# RCMx1_Rev_04.net
KiCad netlist of a schematic drawn in EAGLE
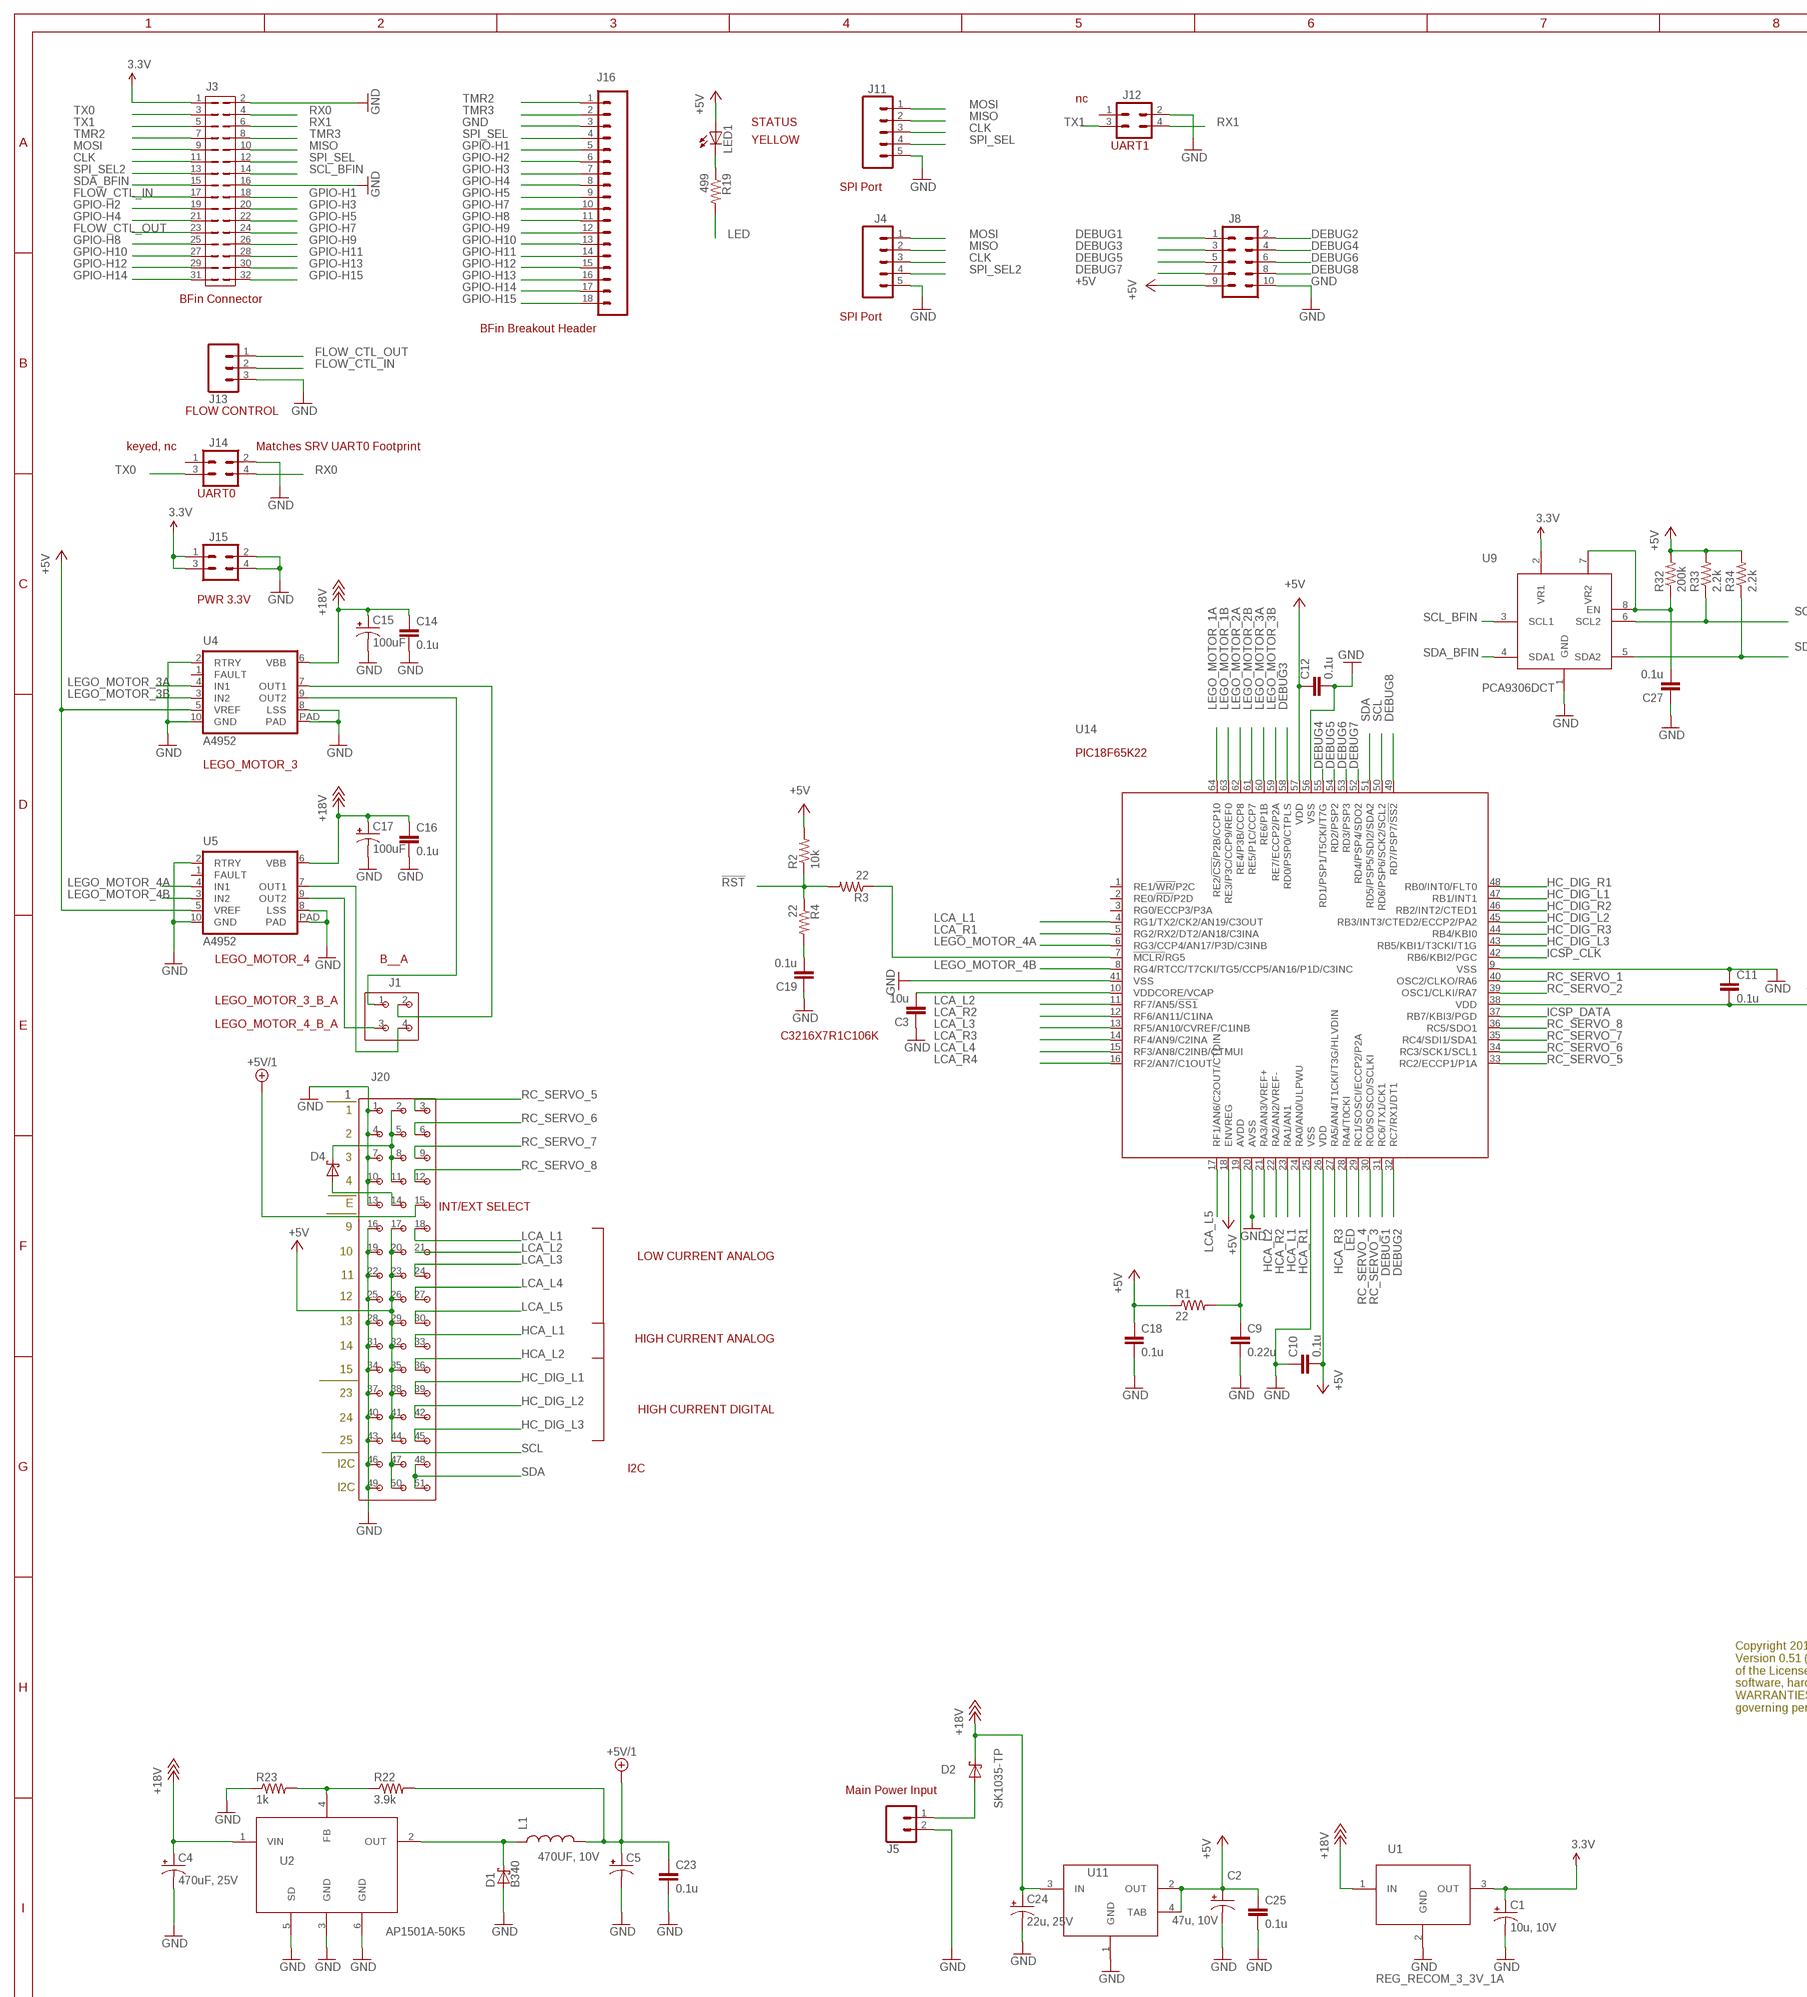
[diagram p0: schematic, sheet 1, part 1 of 2]
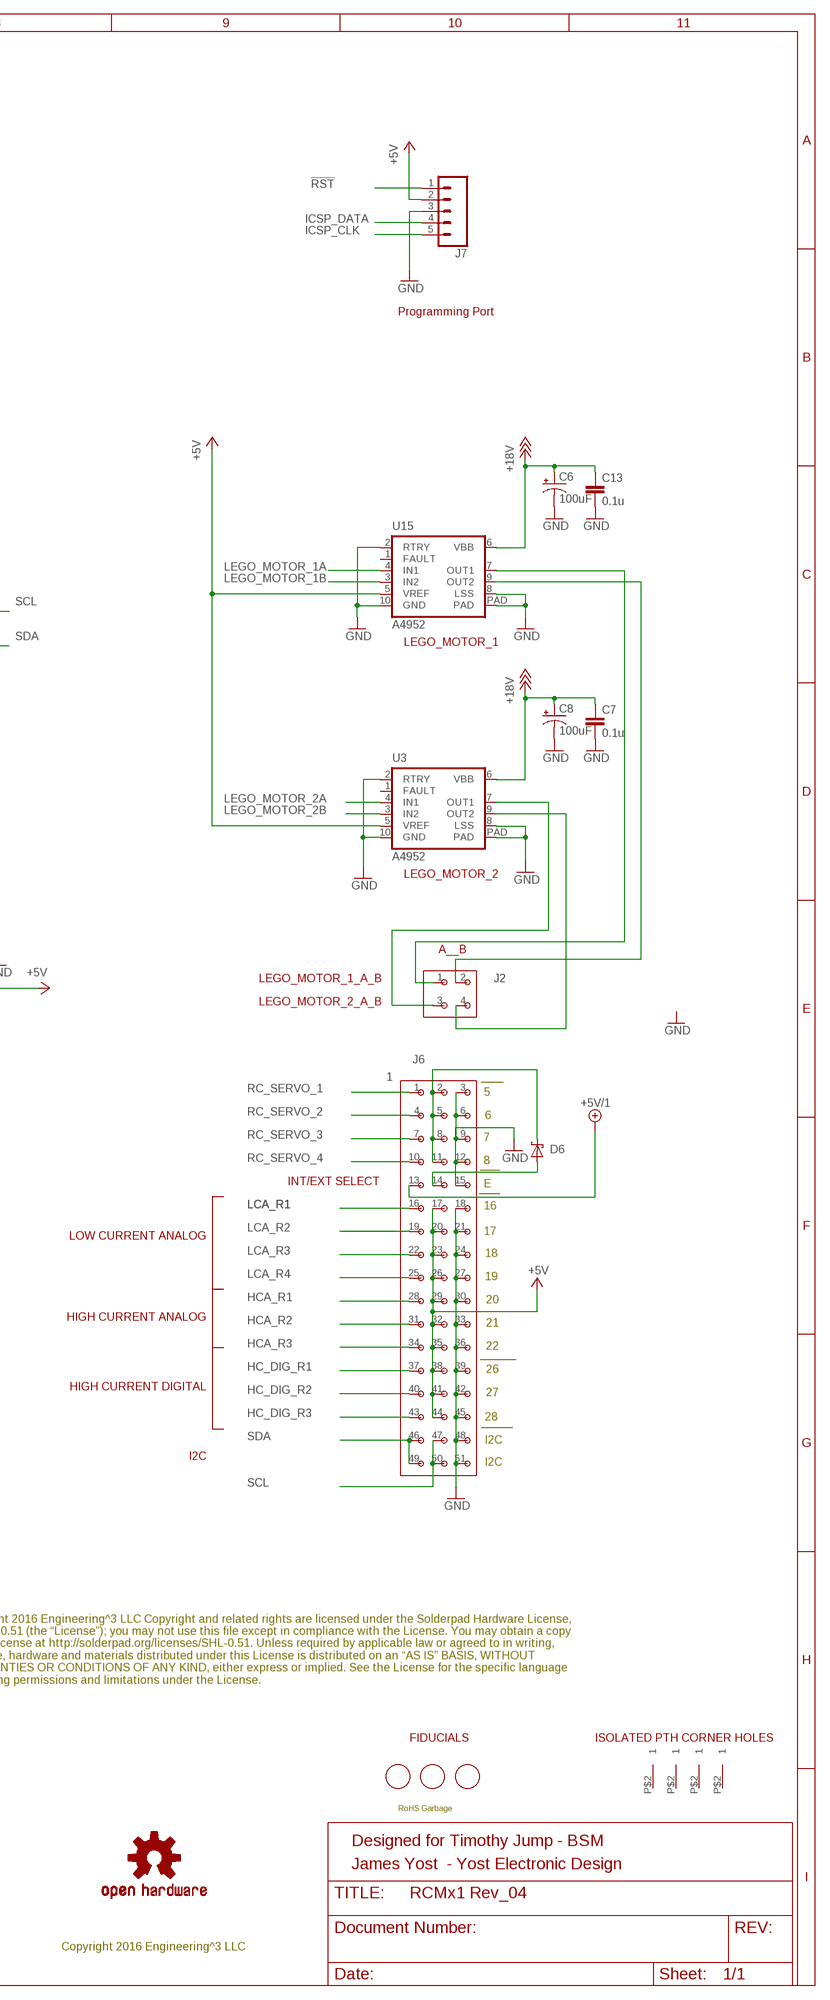
[diagram p1: schematic, sheet 1, part 2 of 2]

(export (version "E")
  (design (tool "Eeschema 10.0.6"))
  (components
    (comp (ref "C1")
      (value "10u, 10V")
      (footprint "eagle-import:EIA3216")
      (libsource (lib "eagle-import") (part "CAP_POL1206"))
    )
    (comp (ref "C2")
      (value "47u, 10V")
      (footprint "eagle-import:CAP1210_POL")
      (libsource (lib "eagle-import") (part "CAP_1210_POL"))
    )
    (comp (ref "C3")
      (value "10u")
      (footprint "eagle-import:1206")
      (libsource (lib "eagle-import") (part "CAP1206"))
    )
    (comp (ref "C4")
      (value "470uF, 25V")
      (footprint "eagle-import:PANASONIC_G")
      (libsource (lib "eagle-import") (part "CAP_POLG"))
    )
    (comp (ref "C5")
      (value "470UF, 10V")
      (footprint "eagle-import:PANASONIC_F")
      (libsource (lib "eagle-import") (part "CAP_ELT_PANASONIC_470UF"))
    )
    (comp (ref "C6")
      (value "100uF")
      (footprint "eagle-import:PANASONIC_D")
      (libsource (lib "eagle-import") (part "CAP_POLD"))
    )
    (comp (ref "C7")
      (value "0.1u")
      (footprint "eagle-import:0805")
      (libsource (lib "eagle-import") (part "CAP0805"))
    )
    (comp (ref "C8")
      (value "100uF")
      (footprint "eagle-import:PANASONIC_D")
      (libsource (lib "eagle-import") (part "CAP_POLD"))
    )
    (comp (ref "C9")
      (value "0.22u")
      (footprint "eagle-import:0805")
      (libsource (lib "eagle-import") (part "CAP0805"))
    )
    (comp (ref "C10")
      (value "0.1u")
      (footprint "eagle-import:0805")
      (libsource (lib "eagle-import") (part "CAP0805"))
    )
    (comp (ref "C11")
      (value "0.1u")
      (footprint "eagle-import:0805")
      (libsource (lib "eagle-import") (part "CAP0805"))
    )
    (comp (ref "C12")
      (value "0.1u")
      (footprint "eagle-import:0805")
      (libsource (lib "eagle-import") (part "CAP0805"))
    )
    (comp (ref "C13")
      (value "0.1u")
      (footprint "eagle-import:0805")
      (libsource (lib "eagle-import") (part "CAP0805"))
    )
    (comp (ref "C14")
      (value "0.1u")
      (footprint "eagle-import:0805")
      (libsource (lib "eagle-import") (part "CAP0805"))
    )
    (comp (ref "C15")
      (value "100uF")
      (footprint "eagle-import:PANASONIC_D")
      (libsource (lib "eagle-import") (part "CAP_POLD"))
    )
    (comp (ref "C16")
      (value "0.1u")
      (footprint "eagle-import:0805")
      (libsource (lib "eagle-import") (part "CAP0805"))
    )
    (comp (ref "C17")
      (value "100uF")
      (footprint "eagle-import:PANASONIC_D")
      (libsource (lib "eagle-import") (part "CAP_POLD"))
    )
    (comp (ref "C18")
      (value "0.1u")
      (footprint "eagle-import:0805")
      (libsource (lib "eagle-import") (part "CAP0805"))
    )
    (comp (ref "C19")
      (value "0.1u")
      (footprint "eagle-import:0805")
      (libsource (lib "eagle-import") (part "CAP0805"))
    )
    (comp (ref "C23")
      (value "0.1u")
      (footprint "eagle-import:0805")
      (libsource (lib "eagle-import") (part "CAP0805"))
    )
    (comp (ref "C24")
      (value "22u, 25V")
      (footprint "eagle-import:CAP1210_POL")
      (libsource (lib "eagle-import") (part "CAP_1210_POL"))
    )
    (comp (ref "C25")
      (value "0.1u")
      (footprint "eagle-import:0805")
      (libsource (lib "eagle-import") (part "CAP0805"))
    )
    (comp (ref "C27")
      (value "0.1u")
      (footprint "eagle-import:0805")
      (libsource (lib "eagle-import") (part "CAP0805"))
    )
    (comp (ref "D1")
      (value "B340")
      (footprint "eagle-import:SMA_DO214AC")
      (libsource (lib "eagle-import") (part "B340"))
    )
    (comp (ref "D2")
      (value "SK1035-TP")
      (footprint "eagle-import:DO214AB")
      (libsource (lib "eagle-import") (part "SK1035-TP"))
    )
    (comp (ref "D4")
      (value "SK1035-TP")
      (footprint "eagle-import:DO214AB")
      (libsource (lib "eagle-import") (part "SK1035-TP"))
    )
    (comp (ref "D6")
      (value "SK1035-TP")
      (footprint "eagle-import:DO214AB")
      (libsource (lib "eagle-import") (part "SK1035-TP"))
    )
    (comp (ref "FID1")
      (value "FIDUCIAL")
      (footprint "eagle-import:FIDUCIAL_1MM")
      (libsource (lib "eagle-import") (part "FIDUCIAL"))
    )
    (comp (ref "FID2")
      (value "FIDUCIAL")
      (footprint "eagle-import:FIDUCIAL_1MM")
      (libsource (lib "eagle-import") (part "FIDUCIAL"))
    )
    (comp (ref "FID3")
      (value "FIDUCIAL")
      (footprint "eagle-import:FIDUCIAL_1MM")
      (libsource (lib "eagle-import") (part "FIDUCIAL"))
    )
    (comp (ref "J1")
      (value "CON_2X2_0_100")
      (footprint "eagle-import:CON_2X2_0_100")
      (libsource (lib "eagle-import") (part "CON_2X2_0_100"))
    )
    (comp (ref "J2")
      (value "CON_2X2_0_100")
      (footprint "eagle-import:CON_2X2_0_100")
      (libsource (lib "eagle-import") (part "CON_2X2_0_100"))
    )
    (comp (ref "J3")
      (value "CON_2X16_0_100")
      (footprint "eagle-import:CON_2X16_0_100")
      (libsource (lib "eagle-import") (part "CON_2X16_0_100"))
    )
    (comp (ref "J4")
      (value "M05PTH")
      (footprint "eagle-import:1X05")
      (libsource (lib "eagle-import") (part "M05PTH"))
    )
    (comp (ref "J5")
      (value "M02NG")
      (footprint "eagle-import:1X02")
      (libsource (lib "eagle-import") (part "M02NG"))
    )
    (comp (ref "J6")
      (value "CON_3X17_0_100")
      (footprint "eagle-import:CON_3X17_0_100")
      (libsource (lib "eagle-import") (part "CON_3X17_0_100"))
    )
    (comp (ref "J7")
      (value "M05PTH")
      (footprint "eagle-import:1X05")
      (libsource (lib "eagle-import") (part "SparkFun-Connectors_M05PTH"))
    )
    (comp (ref "J8")
      (value "M05X2PTH")
      (footprint "eagle-import:AVR_ICSP")
      (libsource (lib "eagle-import") (part "M05X2PTH"))
    )
    (comp (ref "J11")
      (value "M05PTH")
      (footprint "eagle-import:1X05")
      (libsource (lib "eagle-import") (part "M05PTH"))
    )
    (comp (ref "J12")
      (value "CON2X2")
      (footprint "eagle-import:CON2X2")
      (libsource (lib "eagle-import") (part "CON2X2"))
    )
    (comp (ref "J13")
      (value "M03PTH")
      (footprint "eagle-import:1X03")
      (libsource (lib "eagle-import") (part "M03PTH"))
    )
    (comp (ref "J14")
      (value "CON2X2")
      (footprint "eagle-import:CON2X2")
      (libsource (lib "eagle-import") (part "CON2X2"))
    )
    (comp (ref "J15")
      (value "CON2X2")
      (footprint "eagle-import:CON2X2")
      (libsource (lib "eagle-import") (part "CON2X2"))
    )
    (comp (ref "J16")
      (value "CON1X18")
      (footprint "eagle-import:CON1X18")
      (libsource (lib "eagle-import") (part "CON1X18"))
    )
    (comp (ref "J20")
      (value "CON_3X17_0_100")
      (footprint "eagle-import:CON_3X17_0_100")
      (libsource (lib "eagle-import") (part "CON_3X17_0_100"))
    )
    (comp (ref "L1")
      (value "IND_47UH_COILTRONICS_2_95A")
      (footprint "eagle-import:IND_PADS_SMT")
      (libsource (lib "eagle-import") (part "IND_47UH_COILTRONICS_2_95A"))
    )
    (comp (ref "LED1")
      (value "LEDCHIP-LED0805")
      (footprint "eagle-import:CHIP-LED0805")
      (libsource (lib "eagle-import") (part "LEDCHIP-LED0805"))
    )
    (comp (ref "LOGO1")
      (value "OSHW-LOGOM")
      (footprint "eagle-import:OSHW-LOGO-M")
      (libsource (lib "eagle-import") (part "OSHW-LOGOM"))
    )
    (comp (ref "R1")
      (value "22")
      (footprint "eagle-import:0805")
      (libsource (lib "eagle-import") (part "RESISTOR"))
    )
    (comp (ref "R2")
      (value "10k")
      (footprint "eagle-import:0805")
      (libsource (lib "eagle-import") (part "RESISTOR"))
    )
    (comp (ref "R3")
      (value "22")
      (footprint "eagle-import:0805")
      (libsource (lib "eagle-import") (part "RESISTOR"))
    )
    (comp (ref "R4")
      (value "22")
      (footprint "eagle-import:0805")
      (libsource (lib "eagle-import") (part "RESISTOR"))
    )
    (comp (ref "R19")
      (value "499")
      (footprint "eagle-import:0805")
      (libsource (lib "eagle-import") (part "RESISTOR"))
    )
    (comp (ref "R22")
      (value "3.9k")
      (footprint "eagle-import:0805")
      (libsource (lib "eagle-import") (part "RESISTOR"))
    )
    (comp (ref "R23")
      (value "1k")
      (footprint "eagle-import:0805")
      (libsource (lib "eagle-import") (part "RESISTOR"))
    )
    (comp (ref "R32")
      (value "200k")
      (footprint "eagle-import:0805")
      (libsource (lib "eagle-import") (part "RESISTOR"))
    )
    (comp (ref "R33")
      (value "2.2k")
      (footprint "eagle-import:0805")
      (libsource (lib "eagle-import") (part "RESISTOR"))
    )
    (comp (ref "R34")
      (value "2.2k")
      (footprint "eagle-import:0805")
      (libsource (lib "eagle-import") (part "RESISTOR"))
    )
    (comp (ref "U$1")
      (value "GNDPAD")
      (footprint "eagle-import:GNDPAD")
      (libsource (lib "eagle-import") (part "GNDPAD"))
    )
    (comp (ref "U$2")
      (value "GNDPAD")
      (footprint "eagle-import:GNDPAD")
      (libsource (lib "eagle-import") (part "GNDPAD"))
    )
    (comp (ref "U$3")
      (value "ROHS_GARBAGE")
      (footprint "eagle-import:ROHS_GARBAGE_5MM")
      (libsource (lib "eagle-import") (part "ROHS_GARBAGE"))
    )
    (comp (ref "U$7")
      (value "GNDPAD")
      (footprint "eagle-import:GNDPAD")
      (libsource (lib "eagle-import") (part "GNDPAD"))
    )
    (comp (ref "U$8")
      (value "GNDPAD")
      (footprint "eagle-import:GNDPAD")
      (libsource (lib "eagle-import") (part "GNDPAD"))
    )
    (comp (ref "U1")
      (value "REG_RECOM_3_3V_1A")
      (footprint "eagle-import:REG_RECOM_3_3V_1A")
      (libsource (lib "eagle-import") (part "REG_RECOM_3_3V_1A"))
    )
    (comp (ref "U2")
      (value "AP1501A-50K5")
      (footprint "eagle-import:TO263-5")
      (libsource (lib "eagle-import") (part "AP1501A-50K5"))
    )
    (comp (ref "U3")
      (value "A4952")
      (footprint "eagle-import:MSOP10_W_THERMAL_PAD")
      (libsource (lib "eagle-import") (part "A4952"))
    )
    (comp (ref "U4")
      (value "A4952")
      (footprint "eagle-import:MSOP10_W_THERMAL_PAD")
      (libsource (lib "eagle-import") (part "A4952"))
    )
    (comp (ref "U5")
      (value "A4952")
      (footprint "eagle-import:MSOP10_W_THERMAL_PAD")
      (libsource (lib "eagle-import") (part "A4952"))
    )
    (comp (ref "U9")
      (value "PCA9306DCT")
      (footprint "eagle-import:TEST08")
      (libsource (lib "eagle-import") (part "PCA9306DCT"))
    )
    (comp (ref "U11")
      (value "TLV1117-5")
      (footprint "eagle-import:SOT223")
      (libsource (lib "eagle-import") (part "TLV1117-5"))
    )
    (comp (ref "U14")
      (value "MICRO_C_PIC18F65K22")
      (footprint "eagle-import:64PIN_TQFP_10X10X1MM")
      (libsource (lib "eagle-import") (part "MICRO_C_PIC18F65K22"))
    )
    (comp (ref "U15")
      (value "A4952")
      (footprint "eagle-import:MSOP10_W_THERMAL_PAD")
      (libsource (lib "eagle-import") (part "A4952"))
    )
  )
  (nets
    (net (code "1") (name "+5V") (class "Default")
      (node (ref "C10") (pin "2") (pinfunction "2_2") (pintype "passive"))
      (node (ref "C11") (pin "2") (pinfunction "2_2") (pintype "passive"))
      (node (ref "C12") (pin "1") (pinfunction "1_1") (pintype "passive"))
      (node (ref "C18") (pin "1") (pinfunction "1_1") (pintype "passive"))
      (node (ref "C2") (pin "1") (pinfunction "+_1") (pintype "passive"))
      (node (ref "C25") (pin "1") (pinfunction "1_1") (pintype "passive"))
      (node (ref "J20") (pin "17") (pinfunction "17_17") (pintype "passive"))
      (node (ref "J20") (pin "20") (pinfunction "20_20") (pintype "passive"))
      (node (ref "J20") (pin "23") (pinfunction "23_23") (pintype "passive"))
      (node (ref "J20") (pin "26") (pinfunction "26_26") (pintype "passive"))
      (node (ref "J20") (pin "29") (pinfunction "29_29") (pintype "passive"))
      (node (ref "J20") (pin "32") (pinfunction "32_32") (pintype "passive"))
      (node (ref "J20") (pin "35") (pinfunction "35_35") (pintype "passive"))
      (node (ref "J20") (pin "38") (pinfunction "38_38") (pintype "passive"))
      (node (ref "J20") (pin "41") (pinfunction "41_41") (pintype "passive"))
      (node (ref "J20") (pin "44") (pinfunction "44_44") (pintype "passive"))
      (node (ref "J6") (pin "17") (pinfunction "17_17") (pintype "passive"))
      (node (ref "J6") (pin "20") (pinfunction "20_20") (pintype "passive"))
      (node (ref "J6") (pin "23") (pinfunction "23_23") (pintype "passive"))
      (node (ref "J6") (pin "26") (pinfunction "26_26") (pintype "passive"))
      (node (ref "J6") (pin "29") (pinfunction "29_29") (pintype "passive"))
      (node (ref "J6") (pin "32") (pinfunction "32_32") (pintype "passive"))
      (node (ref "J6") (pin "35") (pinfunction "35_35") (pintype "passive"))
      (node (ref "J6") (pin "38") (pinfunction "38_38") (pintype "passive"))
      (node (ref "J6") (pin "41") (pinfunction "41_41") (pintype "passive"))
      (node (ref "J6") (pin "44") (pinfunction "44_44") (pintype "passive"))
      (node (ref "J7") (pin "2") (pinfunction "2_2") (pintype "passive"))
      (node (ref "J8") (pin "9") (pinfunction "9_9") (pintype "passive"))
      (node (ref "LED1") (pin "A") (pinfunction "A_A") (pintype "passive"))
      (node (ref "R1") (pin "1") (pinfunction "1_1") (pintype "passive"))
      (node (ref "R2") (pin "2") (pinfunction "2_2") (pintype "passive"))
      (node (ref "R32") (pin "2") (pinfunction "2_2") (pintype "passive"))
      (node (ref "R33") (pin "2") (pinfunction "2_2") (pintype "passive"))
      (node (ref "R34") (pin "2") (pinfunction "2_2") (pintype "passive"))
      (node (ref "U11") (pin "2") (pinfunction "OUT_2") (pintype "bidirectional"))
      (node (ref "U11") (pin "4") (pinfunction "TAB_4") (pintype "bidirectional"))
      (node (ref "U14") (pin "18") (pinfunction "ENVREG_18") (pintype "input"))
      (node (ref "U14") (pin "26") (pinfunction "VDD_26") (pintype "power_in"))
      (node (ref "U14") (pin "38") (pinfunction "VDD_38") (pintype "power_in"))
      (node (ref "U14") (pin "57") (pinfunction "VDD_57") (pintype "power_in"))
      (node (ref "U15") (pin "5") (pinfunction "VREF_5") (pintype "passive"))
      (node (ref "U3") (pin "5") (pinfunction "VREF_5") (pintype "passive"))
      (node (ref "U4") (pin "5") (pinfunction "VREF_5") (pintype "passive"))
      (node (ref "U5") (pin "5") (pinfunction "VREF_5") (pintype "passive"))
    )
    (net (code "2") (name "+5V{slash}1") (class "Default")
      (node (ref "C23") (pin "1") (pinfunction "1_1") (pintype "passive"))
      (node (ref "C5") (pin "+") (pinfunction "+_+") (pintype "passive"))
      (node (ref "J20") (pin "15") (pinfunction "15_15") (pintype "passive"))
      (node (ref "J6") (pin "13") (pinfunction "13_13") (pintype "passive"))
      (node (ref "L1") (pin "2") (pinfunction "2_2") (pintype "passive"))
      (node (ref "R22") (pin "2") (pinfunction "2_2") (pintype "passive"))
    )
    (net (code "3") (name "+18V") (class "Default")
      (node (ref "C13") (pin "1") (pinfunction "1_1") (pintype "passive"))
      (node (ref "C14") (pin "1") (pinfunction "1_1") (pintype "passive"))
      (node (ref "C15") (pin "+") (pinfunction "+_+") (pintype "passive"))
      (node (ref "C16") (pin "1") (pinfunction "1_1") (pintype "passive"))
      (node (ref "C17") (pin "+") (pinfunction "+_+") (pintype "passive"))
      (node (ref "C24") (pin "1") (pinfunction "+_1") (pintype "passive"))
      (node (ref "C4") (pin "+") (pinfunction "+_+") (pintype "passive"))
      (node (ref "C6") (pin "+") (pinfunction "+_+") (pintype "passive"))
      (node (ref "C7") (pin "1") (pinfunction "1_1") (pintype "passive"))
      (node (ref "C8") (pin "+") (pinfunction "+_+") (pintype "passive"))
      (node (ref "D2") (pin "1") (pinfunction "C_1") (pintype "passive"))
      (node (ref "U1") (pin "1") (pinfunction "IN_1") (pintype "bidirectional"))
      (node (ref "U11") (pin "3") (pinfunction "IN_3") (pintype "bidirectional"))
      (node (ref "U15") (pin "6") (pinfunction "VBB_6") (pintype "input"))
      (node (ref "U2") (pin "1") (pinfunction "VIN_1") (pintype "bidirectional"))
      (node (ref "U3") (pin "6") (pinfunction "VBB_6") (pintype "input"))
      (node (ref "U4") (pin "6") (pinfunction "VBB_6") (pintype "input"))
      (node (ref "U5") (pin "6") (pinfunction "VBB_6") (pintype "input"))
    )
    (net (code "4") (name "/CLK") (class "Default")
      (node (ref "J11") (pin "3") (pinfunction "3_3") (pintype "passive"))
      (node (ref "J3") (pin "11") (pinfunction "11_11") (pintype "passive"))
      (node (ref "J4") (pin "3") (pinfunction "3_3") (pintype "passive"))
    )
    (net (code "5") (name "/DEBUG1") (class "Default")
      (node (ref "J8") (pin "1") (pinfunction "1_1") (pintype "passive"))
      (node (ref "U14") (pin "31") (pinfunction "RC6/TX1/CK1_31") (pintype "bidirectional"))
    )
    (net (code "6") (name "/DEBUG2") (class "Default")
      (node (ref "J8") (pin "2") (pinfunction "2_2") (pintype "passive"))
      (node (ref "U14") (pin "32") (pinfunction "RC7/RX1/DT1_32") (pintype "bidirectional"))
    )
    (net (code "7") (name "/DEBUG3") (class "Default")
      (node (ref "J8") (pin "3") (pinfunction "3_3") (pintype "passive"))
      (node (ref "U14") (pin "58") (pinfunction "RD0/PSP0/CTPLS_58") (pintype "bidirectional"))
    )
    (net (code "8") (name "/DEBUG4") (class "Default")
      (node (ref "J8") (pin "4") (pinfunction "4_4") (pintype "passive"))
      (node (ref "U14") (pin "55") (pinfunction "RD1/PSP1/T5CKI/T7G_55") (pintype "bidirectional"))
    )
    (net (code "9") (name "/DEBUG5") (class "Default")
      (node (ref "J8") (pin "5") (pinfunction "5_5") (pintype "passive"))
      (node (ref "U14") (pin "54") (pinfunction "RD2/PSP2_54") (pintype "bidirectional"))
    )
    (net (code "10") (name "/DEBUG6") (class "Default")
      (node (ref "J8") (pin "6") (pinfunction "6_6") (pintype "passive"))
      (node (ref "U14") (pin "53") (pinfunction "RD3/PSP3_53") (pintype "bidirectional"))
    )
    (net (code "11") (name "/DEBUG7") (class "Default")
      (node (ref "J8") (pin "7") (pinfunction "7_7") (pintype "passive"))
      (node (ref "U14") (pin "52") (pinfunction "RD4/PSP4/SDO2_52") (pintype "bidirectional"))
    )
    (net (code "12") (name "/DEBUG8") (class "Default")
      (node (ref "J8") (pin "8") (pinfunction "8_8") (pintype "passive"))
      (node (ref "U14") (pin "49") (pinfunction "RD7/PSP7/~{SS2}_49") (pintype "bidirectional"))
    )
    (net (code "13") (name "/FLOW_CTL_IN") (class "Default")
      (node (ref "J13") (pin "2") (pinfunction "2_2") (pintype "passive"))
      (node (ref "J3") (pin "17") (pinfunction "17_17") (pintype "passive"))
    )
    (net (code "14") (name "/FLOW_CTL_OUT") (class "Default")
      (node (ref "J13") (pin "1") (pinfunction "1_1") (pintype "passive"))
      (node (ref "J3") (pin "23") (pinfunction "23_23") (pintype "passive"))
    )
    (net (code "15") (name "/GPIO-H1") (class "Default")
      (node (ref "J16") (pin "5") (pinfunction "5_5") (pintype "passive"))
      (node (ref "J3") (pin "18") (pinfunction "18_18") (pintype "passive"))
    )
    (net (code "16") (name "/GPIO-H2") (class "Default")
      (node (ref "J16") (pin "6") (pinfunction "6_6") (pintype "passive"))
      (node (ref "J3") (pin "19") (pinfunction "19_19") (pintype "passive"))
    )
    (net (code "17") (name "/GPIO-H3") (class "Default")
      (node (ref "J16") (pin "7") (pinfunction "7_7") (pintype "passive"))
      (node (ref "J3") (pin "20") (pinfunction "20_20") (pintype "passive"))
    )
    (net (code "18") (name "/GPIO-H4") (class "Default")
      (node (ref "J16") (pin "8") (pinfunction "8_8") (pintype "passive"))
      (node (ref "J3") (pin "21") (pinfunction "21_21") (pintype "passive"))
    )
    (net (code "19") (name "/GPIO-H5") (class "Default")
      (node (ref "J16") (pin "9") (pinfunction "9_9") (pintype "passive"))
      (node (ref "J3") (pin "22") (pinfunction "22_22") (pintype "passive"))
    )
    (net (code "20") (name "/GPIO-H7") (class "Default")
      (node (ref "J16") (pin "10") (pinfunction "10_10") (pintype "passive"))
      (node (ref "J3") (pin "24") (pinfunction "24_24") (pintype "passive"))
    )
    (net (code "21") (name "/GPIO-H8") (class "Default")
      (node (ref "J16") (pin "11") (pinfunction "11_11") (pintype "passive"))
      (node (ref "J3") (pin "25") (pinfunction "25_25") (pintype "passive"))
    )
    (net (code "22") (name "/GPIO-H9") (class "Default")
      (node (ref "J16") (pin "12") (pinfunction "12_12") (pintype "passive"))
      (node (ref "J3") (pin "26") (pinfunction "26_26") (pintype "passive"))
    )
    (net (code "23") (name "/GPIO-H10") (class "Default")
      (node (ref "J16") (pin "13") (pinfunction "13_13") (pintype "passive"))
      (node (ref "J3") (pin "27") (pinfunction "27_27") (pintype "passive"))
    )
    (net (code "24") (name "/GPIO-H11") (class "Default")
      (node (ref "J16") (pin "14") (pinfunction "14_14") (pintype "passive"))
      (node (ref "J3") (pin "28") (pinfunction "28_28") (pintype "passive"))
    )
    (net (code "25") (name "/GPIO-H12") (class "Default")
      (node (ref "J16") (pin "15") (pinfunction "15_15") (pintype "passive"))
      (node (ref "J3") (pin "29") (pinfunction "29_29") (pintype "passive"))
    )
    (net (code "26") (name "/GPIO-H13") (class "Default")
      (node (ref "J16") (pin "16") (pinfunction "16_16") (pintype "passive"))
      (node (ref "J3") (pin "30") (pinfunction "30_30") (pintype "passive"))
    )
    (net (code "27") (name "/GPIO-H14") (class "Default")
      (node (ref "J16") (pin "17") (pinfunction "17_17") (pintype "passive"))
      (node (ref "J3") (pin "31") (pinfunction "31_31") (pintype "passive"))
    )
    (net (code "28") (name "/GPIO-H15") (class "Default")
      (node (ref "J16") (pin "18") (pinfunction "18_18") (pintype "passive"))
      (node (ref "J3") (pin "32") (pinfunction "32_32") (pintype "passive"))
    )
    (net (code "29") (name "/HCA_L1") (class "Default")
      (node (ref "J20") (pin "33") (pinfunction "33_33") (pintype "passive"))
      (node (ref "U14") (pin "23") (pinfunction "RA1/AN1_23") (pintype "bidirectional"))
    )
    (net (code "30") (name "/HCA_L2") (class "Default")
      (node (ref "J20") (pin "36") (pinfunction "36_36") (pintype "passive"))
      (node (ref "U14") (pin "21") (pinfunction "RA3/AN3/VREF+_21") (pintype "bidirectional"))
    )
    (net (code "31") (name "/HCA_R1") (class "Default")
      (node (ref "J6") (pin "28") (pinfunction "28_28") (pintype "passive"))
      (node (ref "U14") (pin "24") (pinfunction "RA0/AN0/ULPWU_24") (pintype "bidirectional"))
    )
    (net (code "32") (name "/HCA_R2") (class "Default")
      (node (ref "J6") (pin "31") (pinfunction "31_31") (pintype "passive"))
      (node (ref "U14") (pin "22") (pinfunction "RA2/AN2/VREF-_22") (pintype "bidirectional"))
    )
    (net (code "33") (name "/HCA_R3") (class "Default")
      (node (ref "J6") (pin "34") (pinfunction "34_34") (pintype "passive"))
      (node (ref "U14") (pin "27") (pinfunction "RA5/AN4/T1CKI/T3G/HLVDIN_27") (pintype "bidirectional"))
    )
    (net (code "34") (name "/HC_DIG_L1") (class "Default")
      (node (ref "J20") (pin "39") (pinfunction "39_39") (pintype "passive"))
      (node (ref "U14") (pin "47") (pinfunction "RB1/INT1_47") (pintype "bidirectional"))
    )
    (net (code "35") (name "/HC_DIG_L2") (class "Default")
      (node (ref "J20") (pin "42") (pinfunction "42_42") (pintype "passive"))
      (node (ref "U14") (pin "45") (pinfunction "RB3/INT3/CTED2/ECCP2/PA2_45") (pintype "bidirectional"))
    )
    (net (code "36") (name "/HC_DIG_L3") (class "Default")
      (node (ref "J20") (pin "45") (pinfunction "45_45") (pintype "passive"))
      (node (ref "U14") (pin "43") (pinfunction "RB5/KBI1/T3CKI/T1G_43") (pintype "bidirectional"))
    )
    (net (code "37") (name "/HC_DIG_R1") (class "Default")
      (node (ref "J6") (pin "37") (pinfunction "37_37") (pintype "passive"))
      (node (ref "U14") (pin "48") (pinfunction "RB0/INT0/FLT0_48") (pintype "bidirectional"))
    )
    (net (code "38") (name "/HC_DIG_R2") (class "Default")
      (node (ref "J6") (pin "40") (pinfunction "40_40") (pintype "passive"))
      (node (ref "U14") (pin "46") (pinfunction "RB2/INT2/CTED1_46") (pintype "bidirectional"))
    )
    (net (code "39") (name "/HC_DIG_R3") (class "Default")
      (node (ref "J6") (pin "43") (pinfunction "43_43") (pintype "passive"))
      (node (ref "U14") (pin "44") (pinfunction "RB4/KBI0_44") (pintype "bidirectional"))
    )
    (net (code "40") (name "/ICSP_CLK") (class "Default")
      (node (ref "J7") (pin "5") (pinfunction "5_5") (pintype "passive"))
      (node (ref "U14") (pin "42") (pinfunction "RB6/KBI2/PGC_42") (pintype "bidirectional"))
    )
    (net (code "41") (name "/ICSP_DATA") (class "Default")
      (node (ref "J7") (pin "4") (pinfunction "4_4") (pintype "passive"))
      (node (ref "U14") (pin "37") (pinfunction "RB7/KBI3/PGD_37") (pintype "bidirectional"))
    )
    (net (code "42") (name "/LCA_L1") (class "Default")
      (node (ref "J20") (pin "18") (pinfunction "18_18") (pintype "passive"))
      (node (ref "U14") (pin "4") (pinfunction "RG1/TX2/CK2/AN19/C3OUT_4") (pintype "bidirectional"))
    )
    (net (code "43") (name "/LCA_L2") (class "Default")
      (node (ref "J20") (pin "21") (pinfunction "21_21") (pintype "passive"))
      (node (ref "U14") (pin "11") (pinfunction "RF7/AN5/~{SS1}_11") (pintype "bidirectional"))
    )
    (net (code "44") (name "/LCA_L3") (class "Default")
      (node (ref "J20") (pin "24") (pinfunction "24_24") (pintype "passive"))
      (node (ref "U14") (pin "13") (pinfunction "RF5/AN10/CVREF/C1INB_13") (pintype "bidirectional"))
    )
    (net (code "45") (name "/LCA_L4") (class "Default")
      (node (ref "J20") (pin "27") (pinfunction "27_27") (pintype "passive"))
      (node (ref "U14") (pin "15") (pinfunction "RF3/AN8/C2INB/CTMUI_15") (pintype "bidirectional"))
    )
    (net (code "46") (name "/LCA_L5") (class "Default")
      (node (ref "J20") (pin "30") (pinfunction "30_30") (pintype "passive"))
      (node (ref "U14") (pin "17") (pinfunction "RF1/AN6/C2OUT/CTDIN_17") (pintype "bidirectional"))
    )
    (net (code "47") (name "/LCA_R1") (class "Default")
      (node (ref "J6") (pin "16") (pinfunction "16_16") (pintype "passive"))
      (node (ref "U14") (pin "5") (pinfunction "RG2/RX2/DT2/AN18/C3INA_5") (pintype "bidirectional"))
    )
    (net (code "48") (name "/LCA_R2") (class "Default")
      (node (ref "J6") (pin "19") (pinfunction "19_19") (pintype "passive"))
      (node (ref "U14") (pin "12") (pinfunction "RF6/AN11/C1INA_12") (pintype "bidirectional"))
    )
    (net (code "49") (name "/LCA_R3") (class "Default")
      (node (ref "J6") (pin "22") (pinfunction "22_22") (pintype "passive"))
      (node (ref "U14") (pin "14") (pinfunction "RF4/AN9/C2INA_14") (pintype "bidirectional"))
    )
    (net (code "50") (name "/LCA_R4") (class "Default")
      (node (ref "J6") (pin "25") (pinfunction "25_25") (pintype "passive"))
      (node (ref "U14") (pin "16") (pinfunction "RF2/AN7/C1OUT_16") (pintype "bidirectional"))
    )
    (net (code "51") (name "/LED") (class "Default")
      (node (ref "R19") (pin "2") (pinfunction "2_2") (pintype "passive"))
      (node (ref "U14") (pin "28") (pinfunction "RA4/T0CKI_28") (pintype "bidirectional"))
    )
    (net (code "52") (name "/LEGO_MOTOR_1A") (class "Default")
      (node (ref "U14") (pin "64") (pinfunction "RE2/~{CS/}P2B/CCP10_64") (pintype "bidirectional"))
      (node (ref "U15") (pin "4") (pinfunction "IN1_4") (pintype "input"))
    )
    (net (code "53") (name "/LEGO_MOTOR_1B") (class "Default")
      (node (ref "U14") (pin "63") (pinfunction "RE3/P3C/CCP9/REF0_63") (pintype "bidirectional"))
      (node (ref "U15") (pin "3") (pinfunction "IN2_3") (pintype "input"))
    )
    (net (code "54") (name "/LEGO_MOTOR_2A") (class "Default")
      (node (ref "U14") (pin "62") (pinfunction "RE4/P3B/CCP8_62") (pintype "bidirectional"))
      (node (ref "U3") (pin "4") (pinfunction "IN1_4") (pintype "input"))
    )
    (net (code "55") (name "/LEGO_MOTOR_2B") (class "Default")
      (node (ref "U14") (pin "61") (pinfunction "RE5/P1C/CCP7_61") (pintype "bidirectional"))
      (node (ref "U3") (pin "3") (pinfunction "IN2_3") (pintype "input"))
    )
    (net (code "56") (name "/LEGO_MOTOR_3A") (class "Default")
      (node (ref "U14") (pin "60") (pinfunction "RE6/P1B_60") (pintype "bidirectional"))
      (node (ref "U4") (pin "4") (pinfunction "IN1_4") (pintype "input"))
    )
    (net (code "57") (name "/LEGO_MOTOR_3B") (class "Default")
      (node (ref "U14") (pin "59") (pinfunction "RE7/ECCP2/P2A_59") (pintype "bidirectional"))
      (node (ref "U4") (pin "3") (pinfunction "IN2_3") (pintype "input"))
    )
    (net (code "58") (name "/LEGO_MOTOR_4A") (class "Default")
      (node (ref "U14") (pin "6") (pinfunction "RG3/CCP4/AN17/P3D/C3INB_6") (pintype "bidirectional"))
      (node (ref "U5") (pin "4") (pinfunction "IN1_4") (pintype "input"))
    )
    (net (code "59") (name "/LEGO_MOTOR_4B") (class "Default")
      (node (ref "U14") (pin "8") (pinfunction "RG4/RTCC/T7CKI/TG5/CCP5/AN16/P1D/C3INC_8") (pintype "bidirectional"))
      (node (ref "U5") (pin "3") (pinfunction "IN2_3") (pintype "input"))
    )
    (net (code "60") (name "/MISO") (class "Default")
      (node (ref "J11") (pin "2") (pinfunction "2_2") (pintype "passive"))
      (node (ref "J3") (pin "10") (pinfunction "10_10") (pintype "passive"))
      (node (ref "J4") (pin "2") (pinfunction "2_2") (pintype "passive"))
    )
    (net (code "61") (name "/MOSI") (class "Default")
      (node (ref "J11") (pin "1") (pinfunction "1_1") (pintype "passive"))
      (node (ref "J3") (pin "9") (pinfunction "9_9") (pintype "passive"))
      (node (ref "J4") (pin "1") (pinfunction "1_1") (pintype "passive"))
    )
    (net (code "62") (name "/RC_SERVO_1") (class "Default")
      (node (ref "J6") (pin "1") (pinfunction "1_1") (pintype "passive"))
      (node (ref "U14") (pin "40") (pinfunction "OSC2/CLKO/RA6_40") (pintype "output"))
    )
    (net (code "63") (name "/RC_SERVO_2") (class "Default")
      (node (ref "J6") (pin "4") (pinfunction "4_4") (pintype "passive"))
      (node (ref "U14") (pin "39") (pinfunction "OSC1/CLKI/RA7_39") (pintype "input"))
    )
    (net (code "64") (name "/RC_SERVO_3") (class "Default")
      (node (ref "J6") (pin "7") (pinfunction "7_7") (pintype "passive"))
      (node (ref "U14") (pin "30") (pinfunction "RC0/SOSCO/SCLKI_30") (pintype "bidirectional"))
    )
    (net (code "65") (name "/RC_SERVO_4") (class "Default")
      (node (ref "J6") (pin "10") (pinfunction "10_10") (pintype "passive"))
      (node (ref "U14") (pin "29") (pinfunction "RC1/SOSCI/ECCP2/P2A_29") (pintype "bidirectional"))
    )
    (net (code "66") (name "/RC_SERVO_5") (class "Default")
      (node (ref "J20") (pin "3") (pinfunction "3_3") (pintype "passive"))
      (node (ref "U14") (pin "33") (pinfunction "RC2/ECCP1/P1A_33") (pintype "bidirectional"))
    )
    (net (code "67") (name "/RC_SERVO_6") (class "Default")
      (node (ref "J20") (pin "6") (pinfunction "6_6") (pintype "passive"))
      (node (ref "U14") (pin "34") (pinfunction "RC3/SCK1/SCL1_34") (pintype "bidirectional"))
    )
    (net (code "68") (name "/RC_SERVO_7") (class "Default")
      (node (ref "J20") (pin "9") (pinfunction "9_9") (pintype "passive"))
      (node (ref "U14") (pin "35") (pinfunction "RC4/SDI1/SDA1_35") (pintype "bidirectional"))
    )
    (net (code "69") (name "/RC_SERVO_8") (class "Default")
      (node (ref "J20") (pin "12") (pinfunction "12_12") (pintype "passive"))
      (node (ref "U14") (pin "36") (pinfunction "RC5/SDO1_36") (pintype "bidirectional"))
    )
    (net (code "70") (name "/RX0") (class "Default")
      (node (ref "J14") (pin "4") (pinfunction "4_4") (pintype "passive"))
      (node (ref "J3") (pin "4") (pinfunction "4_4") (pintype "passive"))
    )
    (net (code "71") (name "/RX1") (class "Default")
      (node (ref "J12") (pin "4") (pinfunction "4_4") (pintype "passive"))
      (node (ref "J3") (pin "6") (pinfunction "6_6") (pintype "passive"))
    )
    (net (code "72") (name "/SCL") (class "Default")
      (node (ref "J20") (pin "47") (pinfunction "47_47") (pintype "passive"))
      (node (ref "J20") (pin "50") (pinfunction "50_50") (pintype "passive"))
      (node (ref "J6") (pin "47") (pinfunction "47_47") (pintype "passive"))
      (node (ref "J6") (pin "50") (pinfunction "50_50") (pintype "passive"))
      (node (ref "R33") (pin "1") (pinfunction "1_1") (pintype "passive"))
      (node (ref "U14") (pin "50") (pinfunction "RD6/PSP6/SCK2/SCL2_50") (pintype "bidirectional"))
      (node (ref "U9") (pin "6") (pinfunction "SCL2_6") (pintype "bidirectional"))
    )
    (net (code "73") (name "/SCL_BFIN") (class "Default")
      (node (ref "J3") (pin "14") (pinfunction "14_14") (pintype "passive"))
      (node (ref "U9") (pin "3") (pinfunction "SCL1_3") (pintype "bidirectional"))
    )
    (net (code "74") (name "/SDA") (class "Default")
      (node (ref "J20") (pin "48") (pinfunction "48_48") (pintype "passive"))
      (node (ref "J20") (pin "51") (pinfunction "51_51") (pintype "passive"))
      (node (ref "J6") (pin "46") (pinfunction "46_46") (pintype "passive"))
      (node (ref "J6") (pin "49") (pinfunction "49_49") (pintype "passive"))
      (node (ref "R34") (pin "1") (pinfunction "1_1") (pintype "passive"))
      (node (ref "U14") (pin "51") (pinfunction "RD5/PSP5/SDI2/SDA2_51") (pintype "bidirectional"))
      (node (ref "U9") (pin "5") (pinfunction "SDA2_5") (pintype "bidirectional"))
    )
    (net (code "75") (name "/SDA_BFIN") (class "Default")
      (node (ref "J3") (pin "15") (pinfunction "15_15") (pintype "passive"))
      (node (ref "U9") (pin "4") (pinfunction "SDA1_4") (pintype "bidirectional"))
    )
    (net (code "76") (name "/SPI_SEL") (class "Default")
      (node (ref "J11") (pin "4") (pinfunction "4_4") (pintype "passive"))
      (node (ref "J16") (pin "4") (pinfunction "4_4") (pintype "passive"))
      (node (ref "J3") (pin "12") (pinfunction "12_12") (pintype "passive"))
    )
    (net (code "77") (name "/SPI_SEL2") (class "Default")
      (node (ref "J3") (pin "13") (pinfunction "13_13") (pintype "passive"))
      (node (ref "J4") (pin "4") (pinfunction "4_4") (pintype "passive"))
    )
    (net (code "78") (name "/TMR2") (class "Default")
      (node (ref "J16") (pin "1") (pinfunction "1_1") (pintype "passive"))
      (node (ref "J3") (pin "7") (pinfunction "7_7") (pintype "passive"))
    )
    (net (code "79") (name "/TMR3") (class "Default")
      (node (ref "J16") (pin "2") (pinfunction "2_2") (pintype "passive"))
      (node (ref "J3") (pin "8") (pinfunction "8_8") (pintype "passive"))
    )
    (net (code "80") (name "/TX0") (class "Default")
      (node (ref "J14") (pin "3") (pinfunction "3_3") (pintype "passive"))
      (node (ref "J3") (pin "3") (pinfunction "3_3") (pintype "passive"))
    )
    (net (code "81") (name "/TX1") (class "Default")
      (node (ref "J12") (pin "3") (pinfunction "3_3") (pintype "passive"))
      (node (ref "J3") (pin "5") (pinfunction "5_5") (pintype "passive"))
    )
    (net (code "82") (name "/~{RST}") (class "Default")
      (node (ref "J7") (pin "1") (pinfunction "1_1") (pintype "passive"))
      (node (ref "R2") (pin "1") (pinfunction "1_1") (pintype "passive"))
      (node (ref "R3") (pin "2") (pinfunction "2_2") (pintype "passive"))
      (node (ref "R4") (pin "1") (pinfunction "1_1") (pintype "passive"))
    )
    (net (code "83") (name "3.3V") (class "Default")
      (node (ref "C1") (pin "A") (pinfunction "+_A") (pintype "passive"))
      (node (ref "J15") (pin "1") (pinfunction "1_1") (pintype "passive"))
      (node (ref "J15") (pin "3") (pinfunction "3_3") (pintype "passive"))
      (node (ref "J3") (pin "1") (pinfunction "1_1") (pintype "passive"))
      (node (ref "U1") (pin "3") (pinfunction "OUT_3") (pintype "bidirectional"))
      (node (ref "U9") (pin "2") (pinfunction "VR1_2") (pintype "bidirectional"))
    )
    (net (code "84") (name "GND") (class "Default")
      (node (ref "C1") (pin "C") (pinfunction "-_C") (pintype "passive"))
      (node (ref "C10") (pin "1") (pinfunction "1_1") (pintype "passive"))
      (node (ref "C11") (pin "1") (pinfunction "1_1") (pintype "passive"))
      (node (ref "C12") (pin "2") (pinfunction "2_2") (pintype "passive"))
      (node (ref "C13") (pin "2") (pinfunction "2_2") (pintype "passive"))
      (node (ref "C14") (pin "2") (pinfunction "2_2") (pintype "passive"))
      (node (ref "C15") (pin "-") (pinfunction "-_-") (pintype "passive"))
      (node (ref "C16") (pin "2") (pinfunction "2_2") (pintype "passive"))
      (node (ref "C17") (pin "-") (pinfunction "-_-") (pintype "passive"))
      (node (ref "C18") (pin "2") (pinfunction "2_2") (pintype "passive"))
      (node (ref "C19") (pin "1") (pinfunction "1_1") (pintype "passive"))
      (node (ref "C2") (pin "2") (pinfunction "-_2") (pintype "passive"))
      (node (ref "C23") (pin "2") (pinfunction "2_2") (pintype "passive"))
      (node (ref "C24") (pin "2") (pinfunction "-_2") (pintype "passive"))
      (node (ref "C25") (pin "2") (pinfunction "2_2") (pintype "passive"))
      (node (ref "C27") (pin "1") (pinfunction "1_1") (pintype "passive"))
      (node (ref "C3") (pin "1") (pinfunction "1_1") (pintype "passive"))
      (node (ref "C4") (pin "-") (pinfunction "-_-") (pintype "passive"))
      (node (ref "C5") (pin "-") (pinfunction "-_-") (pintype "passive"))
      (node (ref "C6") (pin "-") (pinfunction "-_-") (pintype "passive"))
      (node (ref "C7") (pin "2") (pinfunction "2_2") (pintype "passive"))
      (node (ref "C8") (pin "-") (pinfunction "-_-") (pintype "passive"))
      (node (ref "C9") (pin "2") (pinfunction "2_2") (pintype "passive"))
      (node (ref "D1") (pin "A") (pinfunction "A_A") (pintype "passive"))
      (node (ref "J11") (pin "5") (pinfunction "5_5") (pintype "passive"))
      (node (ref "J12") (pin "2") (pinfunction "2_2") (pintype "passive"))
      (node (ref "J13") (pin "3") (pinfunction "3_3") (pintype "passive"))
      (node (ref "J14") (pin "2") (pinfunction "2_2") (pintype "passive"))
      (node (ref "J15") (pin "2") (pinfunction "2_2") (pintype "passive"))
      (node (ref "J15") (pin "4") (pinfunction "4_4") (pintype "passive"))
      (node (ref "J16") (pin "3") (pinfunction "3_3") (pintype "passive"))
      (node (ref "J20") (pin "1") (pinfunction "1_1") (pintype "passive"))
      (node (ref "J20") (pin "10") (pinfunction "10_10") (pintype "passive"))
      (node (ref "J20") (pin "13") (pinfunction "13_13") (pintype "passive"))
      (node (ref "J20") (pin "16") (pinfunction "16_16") (pintype "passive"))
      (node (ref "J20") (pin "19") (pinfunction "19_19") (pintype "passive"))
      (node (ref "J20") (pin "22") (pinfunction "22_22") (pintype "passive"))
      (node (ref "J20") (pin "25") (pinfunction "25_25") (pintype "passive"))
      (node (ref "J20") (pin "28") (pinfunction "28_28") (pintype "passive"))
      (node (ref "J20") (pin "31") (pinfunction "31_31") (pintype "passive"))
      (node (ref "J20") (pin "34") (pinfunction "34_34") (pintype "passive"))
      (node (ref "J20") (pin "37") (pinfunction "37_37") (pintype "passive"))
      (node (ref "J20") (pin "4") (pinfunction "4_4") (pintype "passive"))
      (node (ref "J20") (pin "40") (pinfunction "40_40") (pintype "passive"))
      (node (ref "J20") (pin "43") (pinfunction "43_43") (pintype "passive"))
      (node (ref "J20") (pin "46") (pinfunction "46_46") (pintype "passive"))
      (node (ref "J20") (pin "49") (pinfunction "49_49") (pintype "passive"))
      (node (ref "J20") (pin "7") (pinfunction "7_7") (pintype "passive"))
      (node (ref "J3") (pin "16") (pinfunction "16_16") (pintype "passive"))
      (node (ref "J3") (pin "2") (pinfunction "2_2") (pintype "passive"))
      (node (ref "J4") (pin "5") (pinfunction "5_5") (pintype "passive"))
      (node (ref "J5") (pin "2") (pinfunction "2_2") (pintype "passive"))
      (node (ref "J6") (pin "12") (pinfunction "12_12") (pintype "passive"))
      (node (ref "J6") (pin "15") (pinfunction "15_15") (pintype "passive"))
      (node (ref "J6") (pin "18") (pinfunction "18_18") (pintype "passive"))
      (node (ref "J6") (pin "21") (pinfunction "21_21") (pintype "passive"))
      (node (ref "J6") (pin "24") (pinfunction "24_24") (pintype "passive"))
      (node (ref "J6") (pin "27") (pinfunction "27_27") (pintype "passive"))
      (node (ref "J6") (pin "3") (pinfunction "3_3") (pintype "passive"))
      (node (ref "J6") (pin "30") (pinfunction "30_30") (pintype "passive"))
      (node (ref "J6") (pin "33") (pinfunction "33_33") (pintype "passive"))
      (node (ref "J6") (pin "36") (pinfunction "36_36") (pintype "passive"))
      (node (ref "J6") (pin "39") (pinfunction "39_39") (pintype "passive"))
      (node (ref "J6") (pin "42") (pinfunction "42_42") (pintype "passive"))
      (node (ref "J6") (pin "45") (pinfunction "45_45") (pintype "passive"))
      (node (ref "J6") (pin "48") (pinfunction "48_48") (pintype "passive"))
      (node (ref "J6") (pin "51") (pinfunction "51_51") (pintype "passive"))
      (node (ref "J6") (pin "6") (pinfunction "6_6") (pintype "passive"))
      (node (ref "J6") (pin "9") (pinfunction "9_9") (pintype "passive"))
      (node (ref "J7") (pin "3") (pinfunction "3_3") (pintype "passive"))
      (node (ref "J8") (pin "10") (pinfunction "10_10") (pintype "passive"))
      (node (ref "R23") (pin "1") (pinfunction "1_1") (pintype "passive"))
      (node (ref "U1") (pin "2") (pinfunction "GND_2") (pintype "bidirectional"))
      (node (ref "U11") (pin "1") (pinfunction "GND_1") (pintype "bidirectional"))
      (node (ref "U14") (pin "20") (pinfunction "AVSS_20") (pintype "power_in"))
      (node (ref "U14") (pin "25") (pinfunction "VSS_25") (pintype "power_in"))
      (node (ref "U14") (pin "41") (pinfunction "VSS_41") (pintype "power_in"))
      (node (ref "U14") (pin "56") (pinfunction "VSS_56") (pintype "power_in"))
      (node (ref "U14") (pin "9") (pinfunction "VSS_9") (pintype "power_in"))
      (node (ref "U15") (pin "10") (pinfunction "GND_10") (pintype "power_in"))
      (node (ref "U15") (pin "2") (pinfunction "RTRY_2") (pintype "input"))
      (node (ref "U15") (pin "8") (pinfunction "LSS_8") (pintype "output"))
      (node (ref "U15") (pin "PAD") (pinfunction "PAD_PAD") (pintype "output"))
      (node (ref "U2") (pin "3") (pinfunction "GND_3") (pintype "bidirectional"))
      (node (ref "U2") (pin "5") (pinfunction "SD_5") (pintype "bidirectional"))
      (node (ref "U2") (pin "6") (pinfunction "GND_6") (pintype "bidirectional"))
      (node (ref "U3") (pin "10") (pinfunction "GND_10") (pintype "power_in"))
      (node (ref "U3") (pin "2") (pinfunction "RTRY_2") (pintype "input"))
      (node (ref "U3") (pin "8") (pinfunction "LSS_8") (pintype "output"))
      (node (ref "U3") (pin "PAD") (pinfunction "PAD_PAD") (pintype "output"))
      (node (ref "U4") (pin "10") (pinfunction "GND_10") (pintype "power_in"))
      (node (ref "U4") (pin "2") (pinfunction "RTRY_2") (pintype "input"))
      (node (ref "U4") (pin "8") (pinfunction "LSS_8") (pintype "output"))
      (node (ref "U4") (pin "PAD") (pinfunction "PAD_PAD") (pintype "output"))
      (node (ref "U5") (pin "10") (pinfunction "GND_10") (pintype "power_in"))
      (node (ref "U5") (pin "2") (pinfunction "RTRY_2") (pintype "input"))
      (node (ref "U5") (pin "8") (pinfunction "LSS_8") (pintype "output"))
      (node (ref "U5") (pin "PAD") (pinfunction "PAD_PAD") (pintype "output"))
      (node (ref "U9") (pin "1") (pinfunction "GND_1") (pintype "bidirectional"))
    )
    (net (code "85") (name "Net-(C19-Pad2)") (class "Default")
      (node (ref "C19") (pin "2") (pinfunction "2_2") (pintype "passive"))
      (node (ref "R4") (pin "2") (pinfunction "2_2") (pintype "passive"))
    )
    (net (code "86") (name "Net-(D2-A)") (class "Default")
      (node (ref "D2") (pin "2") (pinfunction "A_2") (pintype "passive"))
      (node (ref "J5") (pin "1") (pinfunction "1_1") (pintype "passive"))
    )
    (net (code "87") (name "Net-(D4-A)") (class "Default")
      (node (ref "D4") (pin "2") (pinfunction "A_2") (pintype "passive"))
      (node (ref "J20") (pin "14") (pinfunction "14_14") (pintype "passive"))
    )
    (net (code "88") (name "Net-(D4-C)") (class "Default")
      (node (ref "D4") (pin "1") (pinfunction "C_1") (pintype "passive"))
      (node (ref "J20") (pin "11") (pinfunction "11_11") (pintype "passive"))
      (node (ref "J20") (pin "2") (pinfunction "2_2") (pintype "passive"))
      (node (ref "J20") (pin "5") (pinfunction "5_5") (pintype "passive"))
      (node (ref "J20") (pin "8") (pinfunction "8_8") (pintype "passive"))
    )
    (net (code "89") (name "Net-(D6-A)") (class "Default")
      (node (ref "D6") (pin "2") (pinfunction "A_2") (pintype "passive"))
      (node (ref "J6") (pin "14") (pinfunction "14_14") (pintype "passive"))
    )
    (net (code "90") (name "Net-(D6-C)") (class "Default")
      (node (ref "D6") (pin "1") (pinfunction "C_1") (pintype "passive"))
      (node (ref "J6") (pin "11") (pinfunction "11_11") (pintype "passive"))
      (node (ref "J6") (pin "2") (pinfunction "2_2") (pintype "passive"))
      (node (ref "J6") (pin "5") (pinfunction "5_5") (pintype "passive"))
      (node (ref "J6") (pin "8") (pinfunction "8_8") (pintype "passive"))
    )
    (net (code "91") (name "Net-(LED1-PadC)") (class "Default")
      (node (ref "LED1") (pin "C") (pinfunction "C_C") (pintype "passive"))
      (node (ref "R19") (pin "1") (pinfunction "1_1") (pintype "passive"))
    )
    (net (code "92") (name "Net-(U2-FB)") (class "Default")
      (node (ref "R22") (pin "1") (pinfunction "1_1") (pintype "passive"))
      (node (ref "R23") (pin "2") (pinfunction "2_2") (pintype "passive"))
      (node (ref "U2") (pin "4") (pinfunction "FB_4") (pintype "bidirectional"))
    )
    (net (code "93") (name "Net-(U2-OUT)") (class "Default")
      (node (ref "D1") (pin "C") (pinfunction "C_C") (pintype "passive"))
      (node (ref "L1") (pin "1") (pinfunction "1_1") (pintype "passive"))
      (node (ref "U2") (pin "2") (pinfunction "OUT_2") (pintype "bidirectional"))
    )
    (net (code "94") (name "Net-(U3-OUT1)") (class "Default")
      (node (ref "J2") (pin "3") (pinfunction "3_3") (pintype "passive"))
      (node (ref "U3") (pin "7") (pinfunction "OUT1_7") (pintype "output"))
    )
    (net (code "95") (name "Net-(U3-OUT2)") (class "Default")
      (node (ref "J2") (pin "4") (pinfunction "4_4") (pintype "passive"))
      (node (ref "U3") (pin "9") (pinfunction "OUT2_9") (pintype "input"))
    )
    (net (code "96") (name "Net-(U4-OUT1)") (class "Default")
      (node (ref "J1") (pin "2") (pinfunction "2_2") (pintype "passive"))
      (node (ref "U4") (pin "7") (pinfunction "OUT1_7") (pintype "output"))
    )
    (net (code "97") (name "Net-(U4-OUT2)") (class "Default")
      (node (ref "J1") (pin "1") (pinfunction "1_1") (pintype "passive"))
      (node (ref "U4") (pin "9") (pinfunction "OUT2_9") (pintype "input"))
    )
    (net (code "98") (name "Net-(U5-OUT1)") (class "Default")
      (node (ref "J1") (pin "4") (pinfunction "4_4") (pintype "passive"))
      (node (ref "U5") (pin "7") (pinfunction "OUT1_7") (pintype "output"))
    )
    (net (code "99") (name "Net-(U5-OUT2)") (class "Default")
      (node (ref "J1") (pin "3") (pinfunction "3_3") (pintype "passive"))
      (node (ref "U5") (pin "9") (pinfunction "OUT2_9") (pintype "input"))
    )
    (net (code "100") (name "Net-(U9-EN)") (class "Default")
      (node (ref "C27") (pin "2") (pinfunction "2_2") (pintype "passive"))
      (node (ref "R32") (pin "1") (pinfunction "1_1") (pintype "passive"))
      (node (ref "U9") (pin "7") (pinfunction "VR2_7") (pintype "bidirectional"))
      (node (ref "U9") (pin "8") (pinfunction "EN_8") (pintype "input"))
    )
    (net (code "101") (name "Net-(U14-AVDD)") (class "Default")
      (node (ref "C9") (pin "1") (pinfunction "1_1") (pintype "passive"))
      (node (ref "R1") (pin "2") (pinfunction "2_2") (pintype "passive"))
      (node (ref "U14") (pin "19") (pinfunction "AVDD_19") (pintype "power_in"))
    )
    (net (code "102") (name "Net-(U14-VDDCORE{slash}VCAP)") (class "Default")
      (node (ref "C3") (pin "2") (pinfunction "2_2") (pintype "passive"))
      (node (ref "U14") (pin "10") (pinfunction "VDDCORE/VCAP_10") (pintype "power_in"))
    )
    (net (code "103") (name "Net-(U14-~{MCLR{slash}}RG5)") (class "Default")
      (node (ref "R3") (pin "1") (pinfunction "1_1") (pintype "passive"))
      (node (ref "U14") (pin "7") (pinfunction "~{MCLR/}RG5_7") (pintype "input"))
    )
    (net (code "104") (name "Net-(U15-OUT1)") (class "Default")
      (node (ref "J2") (pin "1") (pinfunction "1_1") (pintype "passive"))
      (node (ref "U15") (pin "7") (pinfunction "OUT1_7") (pintype "output"))
    )
    (net (code "105") (name "Net-(U15-OUT2)") (class "Default")
      (node (ref "J2") (pin "2") (pinfunction "2_2") (pintype "passive"))
      (node (ref "U15") (pin "9") (pinfunction "OUT2_9") (pintype "input"))
    )
    (net (code "106") (name "unconnected-(J12-Pad1)") (class "Default")
      (node (ref "J12") (pin "1") (pinfunction "1_1") (pintype "passive"))
    )
    (net (code "107") (name "unconnected-(J14-Pad1)") (class "Default")
      (node (ref "J14") (pin "1") (pinfunction "1_1") (pintype "passive"))
    )
    (net (code "108") (name "unconnected-(U$1-1-PadP$2)") (class "Default")
      (node (ref "U$1") (pin "P$2") (pinfunction "1_P$2") (pintype "bidirectional"))
    )
    (net (code "109") (name "unconnected-(U$2-1-PadP$2)") (class "Default")
      (node (ref "U$2") (pin "P$2") (pinfunction "1_P$2") (pintype "bidirectional"))
    )
    (net (code "110") (name "unconnected-(U$7-1-PadP$2)") (class "Default")
      (node (ref "U$7") (pin "P$2") (pinfunction "1_P$2") (pintype "bidirectional"))
    )
    (net (code "111") (name "unconnected-(U$8-1-PadP$2)") (class "Default")
      (node (ref "U$8") (pin "P$2") (pinfunction "1_P$2") (pintype "bidirectional"))
    )
    (net (code "112") (name "unconnected-(U3-FAULT-Pad1)") (class "Default")
      (node (ref "U3") (pin "1") (pinfunction "FAULT_1") (pintype "output"))
    )
    (net (code "113") (name "unconnected-(U4-FAULT-Pad1)") (class "Default")
      (node (ref "U4") (pin "1") (pinfunction "FAULT_1") (pintype "output"))
    )
    (net (code "114") (name "unconnected-(U5-FAULT-Pad1)") (class "Default")
      (node (ref "U5") (pin "1") (pinfunction "FAULT_1") (pintype "output"))
    )
    (net (code "115") (name "unconnected-(U14-RE0{slash}~{RD{slash}}P2D-Pad2)") (class "Default")
      (node (ref "U14") (pin "2") (pinfunction "RE0/~{RD/}P2D_2") (pintype "bidirectional"))
    )
    (net (code "116") (name "unconnected-(U14-RE1{slash}~{WR{slash}}P2C-Pad1)") (class "Default")
      (node (ref "U14") (pin "1") (pinfunction "RE1/~{WR/}P2C_1") (pintype "bidirectional"))
    )
    (net (code "117") (name "unconnected-(U14-RG0{slash}ECCP3{slash}P3A-Pad3)") (class "Default")
      (node (ref "U14") (pin "3") (pinfunction "RG0/ECCP3/P3A_3") (pintype "bidirectional"))
    )
    (net (code "118") (name "unconnected-(U15-FAULT-Pad1)") (class "Default")
      (node (ref "U15") (pin "1") (pinfunction "FAULT_1") (pintype "output"))
    )
  )
)
